# SiLabs2TC.net
KiCad netlist of a schematic drawn in EAGLE
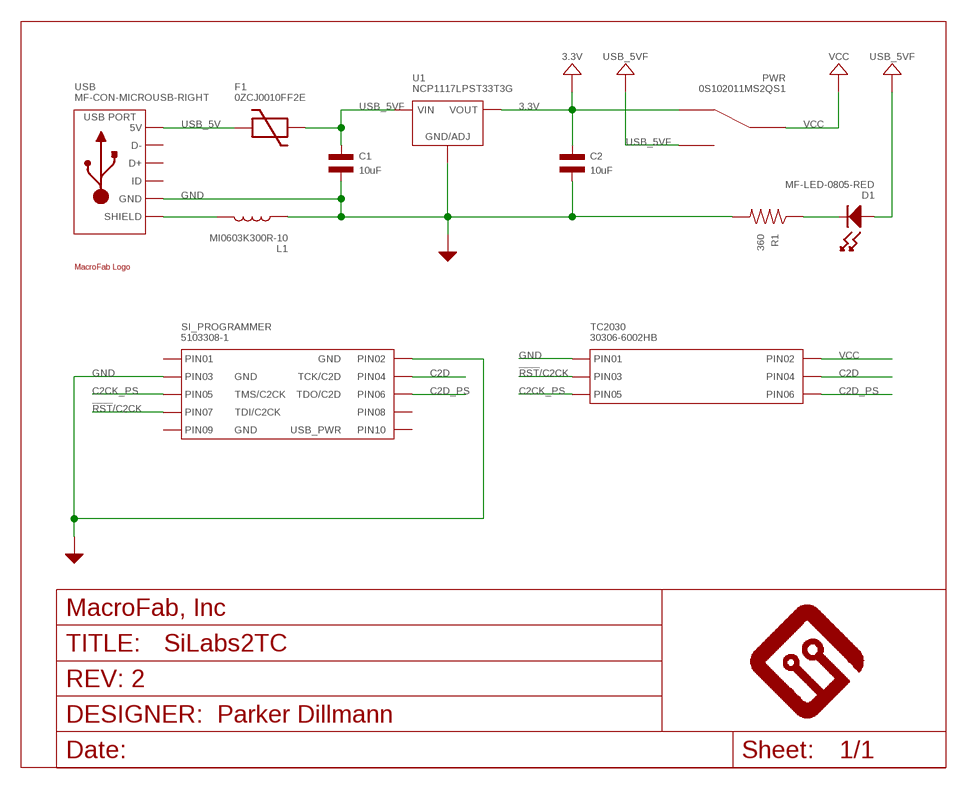
[diagram p0: schematic, sheet 1]

(export (version "E")
  (design (tool "Eeschema 10.0.6"))
  (components
    (comp (ref "C1")
      (value "10uF")
      (footprint "eagle-import:C1206")
      (fields (field (name "MPN") "MF-CAP-1206-10uF"))
      (libsource (lib "eagle-import") (part "CAPACITOR_NP_1206"))
    )
    (comp (ref "C2")
      (value "10uF")
      (footprint "eagle-import:C1206")
      (fields (field (name "MPN") "MF-CAP-1206-10uF"))
      (libsource (lib "eagle-import") (part "CAPACITOR_NP_1206"))
    )
    (comp (ref "D1")
      (value "MF-LED-0805-RED")
      (footprint "eagle-import:LED0805")
      (fields (field (name "HOUSEPART") "YES"))
      (libsource (lib "eagle-import") (part "LED_SINGLE-0805-RED"))
    )
    (comp (ref "F1")
      (value "0ZCJ0010FF2E")
      (footprint "eagle-import:1206")
      (libsource (lib "eagle-import") (part "PTC_FUSE_1206"))
    )
    (comp (ref "FRAME1")
      (value "MF_FRAMEDEFAULT")
      (footprint "eagle-import:MF_FRAME_DEFAULT")
      (fields
        (field (name "HOUSEPART") "0")
        (field (name "DNAME") "Parker Dillmann")
        (field (name "REVNUM") "REV: 2")
      )
      (libsource (lib "eagle-import") (part "MF_FRAMEDEFAULT"))
    )
    (comp (ref "L1")
      (value "MI0603K300R-10")
      (footprint "eagle-import:L0603")
      (fields (field (name "MPN") "MI0603K300R-10"))
      (libsource (lib "eagle-import") (part "INDUCTOR_0603"))
    )
    (comp (ref "PWR")
      (value "0S102011MS2QS1")
      (footprint "eagle-import:0S102011MS2QS1")
      (libsource (lib "eagle-import") (part "SPDT_0S102011MS2QS1"))
    )
    (comp (ref "R1")
      (value "360")
      (footprint "eagle-import:R0805")
      (fields (field (name "MPN") "MF-RES-0805-360"))
      (libsource (lib "eagle-import") (part "RESISTOR_0805"))
    )
    (comp (ref "SI_PROGRAMMER")
      (value "5103308-1")
      (footprint "eagle-import:5103308-1")
      (fields
        (field (name "LABEL02") "GND")
        (field (name "LABEL03") "GND")
        (field (name "LABEL04") "TCK/C2D")
        (field (name "LABEL05") "TMS/C2CK")
        (field (name "LABEL06") "TDO/C2D")
        (field (name "LABEL07") "TDI/C2CK")
        (field (name "LABEL09") "GND")
        (field (name "LABEL10") "USB_PWR")
        (field (name "MPN") "5103308-1")
        (field (name "POPULATE") "1")
      )
      (libsource (lib "eagle-import") (part "CON_02X05_5103308-1"))
    )
    (comp (ref "TC2030")
      (value "30306-6002HB")
      (footprint "eagle-import:30306-6002HB")
      (fields (field (name "MPN") "30306-6002HB") (field (name "POPULATE") "1"))
      (libsource (lib "eagle-import") (part "CON_02X03_30306-6002HB"))
    )
    (comp (ref "U$3")
      (value "MF_LOGOLOGO_MEDIUM")
      (footprint "eagle-import:MF_LOGO_MEDIUM")
      (libsource (lib "eagle-import") (part "MF_LOGOLOGO_MEDIUM"))
    )
    (comp (ref "U1")
      (value "NCP1117LPST33T3G")
      (footprint "eagle-import:SOT-223-3")
      (fields (field (name "HOUSEPART") "NO"))
      (libsource (lib "eagle-import") (part "NCP1117LPST33T3G"))
    )
    (comp (ref "USB")
      (value "MF-CON-MICROUSB-RIGHT")
      (footprint "eagle-import:MICROUSB-RIGHT")
      (fields (field (name "HOUSEPART") "YES"))
      (libsource (lib "eagle-import") (part "USB_MICRO_RIGHT"))
    )
  )
  (nets
    (net (code "1") (name "/C2CK_PS") (class "Default")
      (node (ref "SI_PROGRAMMER") (pin "5") (pinfunction "PIN5_5") (pintype "bidirectional"))
      (node (ref "TC2030") (pin "5") (pinfunction "PIN5_5") (pintype "bidirectional"))
    )
    (net (code "2") (name "/C2D") (class "Default")
      (node (ref "SI_PROGRAMMER") (pin "4") (pinfunction "PIN4_4") (pintype "bidirectional"))
      (node (ref "TC2030") (pin "4") (pinfunction "PIN4_4") (pintype "bidirectional"))
    )
    (net (code "3") (name "/C2D_PS") (class "Default")
      (node (ref "SI_PROGRAMMER") (pin "6") (pinfunction "PIN6_6") (pintype "bidirectional"))
      (node (ref "TC2030") (pin "6") (pinfunction "PIN6_6") (pintype "bidirectional"))
    )
    (net (code "4") (name "/USB_5V") (class "Default")
      (node (ref "F1") (pin "1") (pinfunction "P$1_1") (pintype "bidirectional"))
      (node (ref "USB") (pin "1") (pinfunction "5V_1") (pintype "power_in"))
    )
    (net (code "5") (name "/~{RST}{slash}C2CK") (class "Default")
      (node (ref "SI_PROGRAMMER") (pin "7") (pinfunction "PIN7_7") (pintype "bidirectional"))
      (node (ref "TC2030") (pin "3") (pinfunction "PIN3_3") (pintype "bidirectional"))
    )
    (net (code "6") (name "3.3V") (class "Default")
      (node (ref "C2") (pin "P$1") (pinfunction "P$1_P$1") (pintype "passive"))
      (node (ref "PWR") (pin "1") (pinfunction "1_1") (pintype "bidirectional"))
      (node (ref "U1") (pin "P$1") (pinfunction "VOUT_P$1") (pintype "bidirectional"))
      (node (ref "U1") (pin "P$3") (pinfunction "VOUT_P$3") (pintype "bidirectional"))
    )
    (net (code "7") (name "GND_RAIL") (class "Default")
      (node (ref "C1") (pin "P$2") (pinfunction "P$2_P$2") (pintype "passive"))
      (node (ref "C2") (pin "P$2") (pinfunction "P$2_P$2") (pintype "passive"))
      (node (ref "L1") (pin "P$1") (pinfunction "P$1_P$1") (pintype "passive"))
      (node (ref "R1") (pin "P$2") (pinfunction "P$2_P$2") (pintype "passive"))
      (node (ref "SI_PROGRAMMER") (pin "2") (pinfunction "PIN2_2") (pintype "bidirectional"))
      (node (ref "SI_PROGRAMMER") (pin "3") (pinfunction "PIN3_3") (pintype "bidirectional"))
      (node (ref "TC2030") (pin "1") (pinfunction "PIN1_1") (pintype "bidirectional"))
      (node (ref "U1") (pin "P$2") (pinfunction "GND/ADJ_P$2") (pintype "bidirectional"))
      (node (ref "USB") (pin "5") (pinfunction "GND_5") (pintype "power_in"))
    )
    (net (code "8") (name "Net-(D1-PadCATHODE)") (class "Default")
      (node (ref "D1") (pin "CATHODE") (pinfunction "CATHODE_CATHODE") (pintype "power_in"))
      (node (ref "R1") (pin "P$1") (pinfunction "P$1_P$1") (pintype "passive"))
    )
    (net (code "9") (name "Net-(L1-PadP$2)") (class "Default")
      (node (ref "L1") (pin "P$2") (pinfunction "P$2_P$2") (pintype "passive"))
      (node (ref "USB") (pin "S1") (pinfunction "SLD_S1") (pintype "power_in"))
      (node (ref "USB") (pin "S2") (pinfunction "SLD_S2") (pintype "power_in"))
      (node (ref "USB") (pin "S3") (pinfunction "SLD_S3") (pintype "power_in"))
      (node (ref "USB") (pin "S4") (pinfunction "SLD_S4") (pintype "power_in"))
      (node (ref "USB") (pin "S5") (pinfunction "SLD_S5") (pintype "power_in"))
      (node (ref "USB") (pin "S6") (pinfunction "SLD_S6") (pintype "power_in"))
    )
    (net (code "10") (name "USB_5VF") (class "Default")
      (node (ref "C1") (pin "P$1") (pinfunction "P$1_P$1") (pintype "passive"))
      (node (ref "D1") (pin "ANODE") (pinfunction "ANODE_ANODE") (pintype "power_in"))
      (node (ref "F1") (pin "2") (pinfunction "P$2_2") (pintype "bidirectional"))
      (node (ref "PWR") (pin "3") (pinfunction "2_3") (pintype "bidirectional"))
      (node (ref "U1") (pin "P$4") (pinfunction "VIN_P$4") (pintype "bidirectional"))
    )
    (net (code "11") (name "VCC") (class "Default")
      (node (ref "PWR") (pin "2") (pinfunction "C_2") (pintype "bidirectional"))
      (node (ref "TC2030") (pin "2") (pinfunction "PIN2_2") (pintype "bidirectional"))
    )
    (net (code "12") (name "unconnected-(SI_PROGRAMMER-PIN1-Pad1)") (class "Default")
      (node (ref "SI_PROGRAMMER") (pin "1") (pinfunction "PIN1_1") (pintype "bidirectional"))
    )
    (net (code "13") (name "unconnected-(SI_PROGRAMMER-PIN8-Pad8)") (class "Default")
      (node (ref "SI_PROGRAMMER") (pin "8") (pinfunction "PIN8_8") (pintype "bidirectional"))
    )
    (net (code "14") (name "unconnected-(SI_PROGRAMMER-PIN9-Pad9)") (class "Default")
      (node (ref "SI_PROGRAMMER") (pin "9") (pinfunction "PIN9_9") (pintype "bidirectional"))
    )
    (net (code "15") (name "unconnected-(SI_PROGRAMMER-PIN10-Pad10)") (class "Default")
      (node (ref "SI_PROGRAMMER") (pin "10") (pinfunction "PIN10_10") (pintype "bidirectional"))
    )
    (net (code "16") (name "unconnected-(USB-D+-Pad3)") (class "Default")
      (node (ref "USB") (pin "3") (pinfunction "D+_3") (pintype "bidirectional"))
    )
    (net (code "17") (name "unconnected-(USB-D--Pad2)") (class "Default")
      (node (ref "USB") (pin "2") (pinfunction "D-_2") (pintype "bidirectional"))
    )
    (net (code "18") (name "unconnected-(USB-ID-Pad4)") (class "Default")
      (node (ref "USB") (pin "4") (pinfunction "ID_4") (pintype "bidirectional"))
    )
  )
)
